# Sheet1.net
KiCad netlist of a schematic drawn in Altium Designer
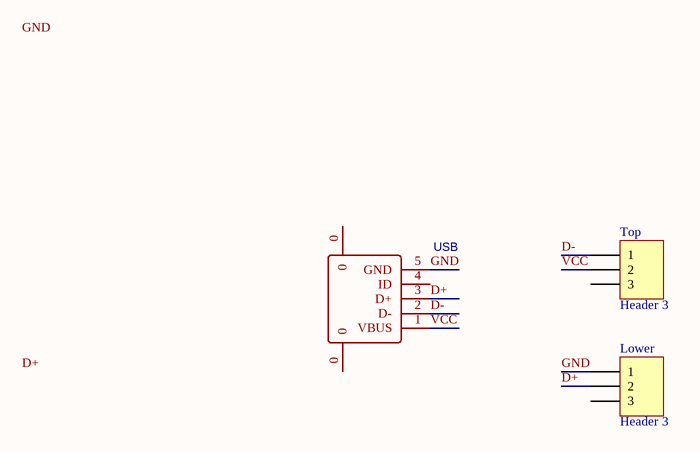
[diagram p0: Sheet1.SchDoc]

(export (version "E")
  (design (tool "Eeschema 10.0.6"))
  (components
    (comp (ref "Lower")
      (value "Header 3")
      (footprint "HDR1X3")
      (description "Header, 3-Pin")
      (fields (field (name "PUBLISHER") "Altium Limited"))
      (libsource (lib "Miscellaneous Connectors") (part "Header 3"))
    )
    (comp (ref "Top")
      (value "Header 3")
      (footprint "HDR1X3")
      (description "Header, 3-Pin")
      (fields (field (name "PUBLISHER") "Altium Limited"))
      (libsource (lib "Miscellaneous Connectors") (part "Header 3"))
    )
    (comp (ref "USB")
      (value "~")
      (footprint "MICROUSB-5S")
      (libsource (lib "micro_USB_lib") (part "Micro USB 母座 5P"))
    )
  )
  (nets
    (net (code "1") (name "/D+") (class "Default")
      (node (ref "Lower") (pin "2") (pinfunction "2_2") (pintype "passive"))
      (node (ref "USB") (pin "3") (pinfunction "D+_3") (pintype "passive"))
    )
    (net (code "2") (name "/D-") (class "Default")
      (node (ref "Top") (pin "1") (pinfunction "1_1") (pintype "passive"))
      (node (ref "USB") (pin "2") (pinfunction "D-_2") (pintype "passive"))
    )
    (net (code "3") (name "/GND") (class "Default")
      (node (ref "Lower") (pin "1") (pinfunction "1_1") (pintype "passive"))
      (node (ref "USB") (pin "5") (pinfunction "GND_5") (pintype "passive"))
    )
    (net (code "4") (name "/VCC") (class "Default")
      (node (ref "Top") (pin "2") (pinfunction "2_2") (pintype "passive"))
      (node (ref "USB") (pin "1") (pinfunction "VBUS_1") (pintype "passive"))
    )
    (net (code "5") (name "unconnected-(Lower-Pad3)") (class "Default")
      (node (ref "Lower") (pin "3") (pinfunction "3_3") (pintype "passive"))
    )
    (net (code "6") (name "unconnected-(Top-Pad3)") (class "Default")
      (node (ref "Top") (pin "3") (pinfunction "3_3") (pintype "passive"))
    )
    (net (code "7") (name "unconnected-(USB-ID-Pad4)") (class "Default")
      (node (ref "USB") (pin "4") (pinfunction "ID_4") (pintype "passive"))
    )
    (net (code "8") (name "unconnected-(USB-Pad0)") (class "Default")
      (node (ref "USB") (pin "0") (pinfunction "0_0") (pintype "passive"))
    )
    (net (code "9") (name "unconnected-(USB-Pad0)_1") (class "Default")
      (node (ref "USB") (pin "0") (pinfunction "0_0") (pintype "passive"))
    )
  )
)
